# hamilton.net
KiCad netlist of a schematic drawn in EAGLE
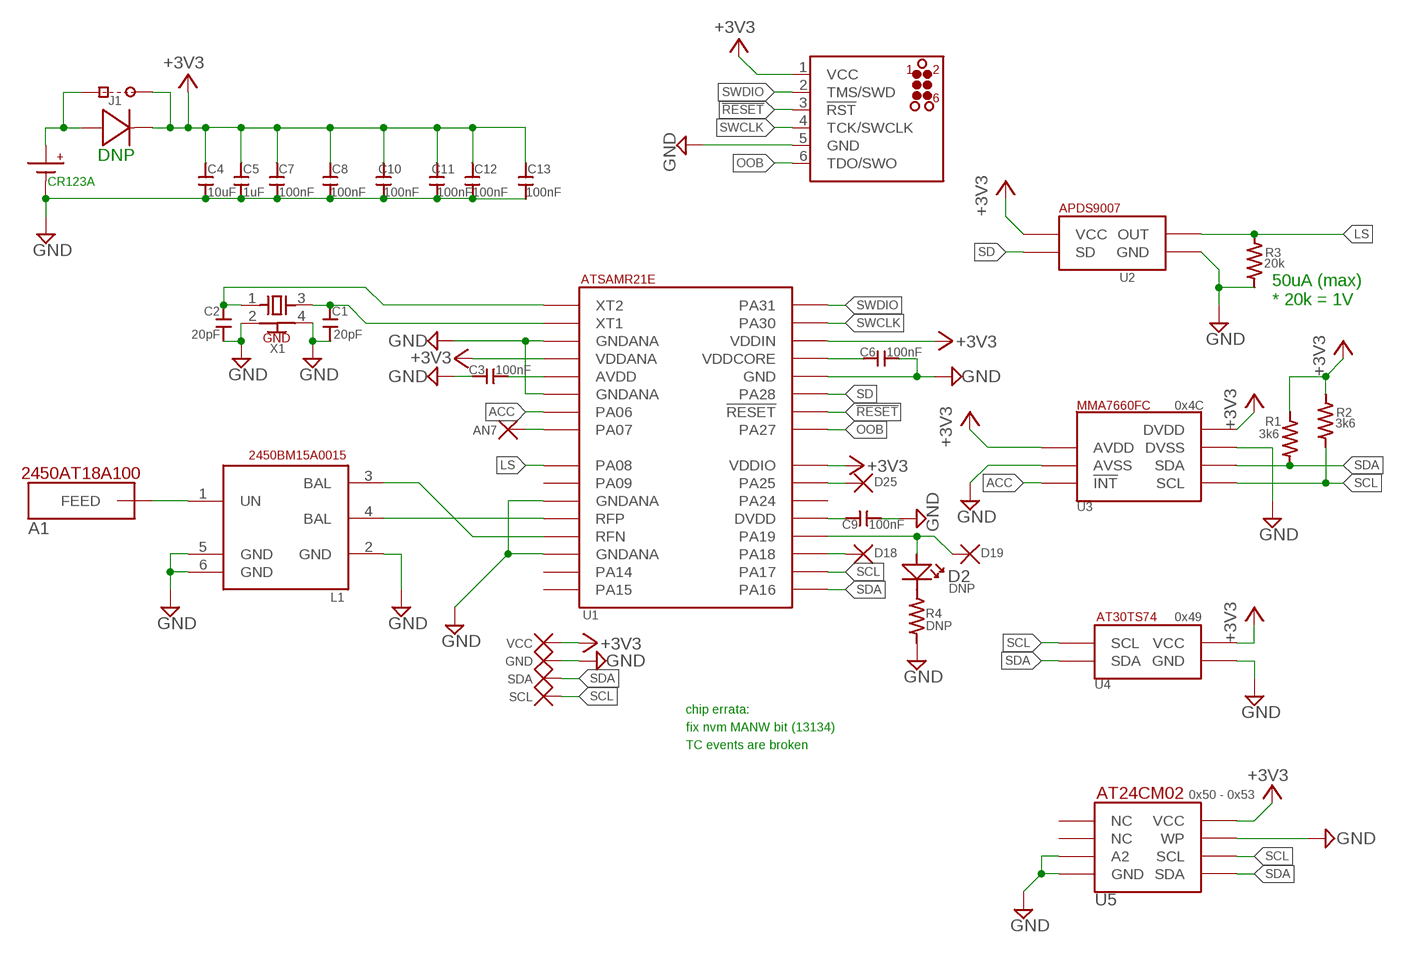
[diagram p0: schematic, sheet 1]

(export (version "E")
  (design (tool "Eeschema 10.0.6"))
  (components
    (comp (ref "A1")
      (value "JOHANSON_ANTENNA2")
      (footprint "eagle-import:JOHANSON_ANTENNA2")
      (libsource (lib "eagle-import") (part "JOHANSON_ANTENNA2"))
    )
    (comp (ref "BT1")
      (value "2/3A")
      (footprint "eagle-import:2_3A")
      (libsource (lib "eagle-import") (part "2/3A"))
    )
    (comp (ref "C1")
      (value "20pF")
      (footprint "eagle-import:S0402")
      (libsource (lib "eagle-import") (part "0603_CAPACITORSMALL"))
    )
    (comp (ref "C2")
      (value "20pF")
      (footprint "eagle-import:S0402")
      (libsource (lib "eagle-import") (part "0603_CAPACITORSMALL"))
    )
    (comp (ref "C3")
      (value "100nF")
      (footprint "eagle-import:C0402")
      (libsource (lib "eagle-import") (part "0603_CAPACITOR0402"))
    )
    (comp (ref "C4")
      (value "10uF")
      (footprint "eagle-import:0805")
      (libsource (lib "eagle-import") (part "0805_CAPACITOR"))
    )
    (comp (ref "C5")
      (value "1uF")
      (footprint "eagle-import:C0402")
      (libsource (lib "eagle-import") (part "0603_CAPACITOR0402"))
    )
    (comp (ref "C6")
      (value "100nF")
      (footprint "eagle-import:C0402")
      (libsource (lib "eagle-import") (part "0603_CAPACITOR0402"))
    )
    (comp (ref "C7")
      (value "100nF")
      (footprint "eagle-import:C0402")
      (libsource (lib "eagle-import") (part "0603_CAPACITOR0402"))
    )
    (comp (ref "C8")
      (value "100nF")
      (footprint "eagle-import:C0402")
      (libsource (lib "eagle-import") (part "0603_CAPACITOR0402"))
    )
    (comp (ref "C9")
      (value "100nF")
      (footprint "eagle-import:C0402")
      (libsource (lib "eagle-import") (part "0603_CAPACITOR0402"))
    )
    (comp (ref "C10")
      (value "100nF")
      (footprint "eagle-import:C0402")
      (libsource (lib "eagle-import") (part "0603_CAPACITOR0402"))
    )
    (comp (ref "C11")
      (value "100nF")
      (footprint "eagle-import:C0402")
      (libsource (lib "eagle-import") (part "0603_CAPACITOR0402"))
    )
    (comp (ref "C12")
      (value "100nF")
      (footprint "eagle-import:C0402")
      (libsource (lib "eagle-import") (part "0603_CAPACITOR0402"))
    )
    (comp (ref "C13")
      (value "100nF")
      (footprint "eagle-import:C0402")
      (libsource (lib "eagle-import") (part "0603_CAPACITOR0402"))
    )
    (comp (ref "D1")
      (value "SOD523F")
      (footprint "eagle-import:SOD523F")
      (libsource (lib "eagle-import") (part "SOD523F"))
    )
    (comp (ref "D2")
      (value "DNP")
      (footprint "eagle-import:LINE_0805")
      (libsource (lib "eagle-import") (part "STATLED"))
    )
    (comp (ref "J1")
      (value "CUTJ2")
      (footprint "eagle-import:CUT3")
      (libsource (lib "eagle-import") (part "CUTJ2"))
    )
    (comp (ref "L1")
      (value "BALUN_JOHANSON")
      (footprint "eagle-import:BALUN_JOHANSON")
      (libsource (lib "eagle-import") (part "BALUN_JOHANSON"))
    )
    (comp (ref "R1")
      (value "3k6")
      (footprint "eagle-import:S0402")
      (libsource (lib "eagle-import") (part "0603_RESISTORSMALL"))
    )
    (comp (ref "R2")
      (value "3k6")
      (footprint "eagle-import:S0402")
      (libsource (lib "eagle-import") (part "0603_RESISTORSMALL"))
    )
    (comp (ref "R3")
      (value "20k")
      (footprint "eagle-import:S0402")
      (libsource (lib "eagle-import") (part "0603_RESISTORSMALL"))
    )
    (comp (ref "R4")
      (value "DNP")
      (footprint "eagle-import:S0402")
      (libsource (lib "eagle-import") (part "0603_RESISTORSMALL"))
    )
    (comp (ref "TP1")
      (value "D19")
      (footprint "eagle-import:TPP")
      (libsource (lib "eagle-import") (part "TP"))
    )
    (comp (ref "TP2")
      (value "D18")
      (footprint "eagle-import:TPP")
      (libsource (lib "eagle-import") (part "TP"))
    )
    (comp (ref "TP3")
      (value "AN7")
      (footprint "eagle-import:TPP")
      (libsource (lib "eagle-import") (part "TP"))
    )
    (comp (ref "TP4")
      (value "D25")
      (footprint "eagle-import:TPP")
      (libsource (lib "eagle-import") (part "TP"))
    )
    (comp (ref "TP5")
      (value "VCC")
      (footprint "eagle-import:TPP")
      (libsource (lib "eagle-import") (part "TP"))
    )
    (comp (ref "TP6")
      (value "GND")
      (footprint "eagle-import:TPP")
      (libsource (lib "eagle-import") (part "TP"))
    )
    (comp (ref "TP7")
      (value "SDA")
      (footprint "eagle-import:TPP")
      (libsource (lib "eagle-import") (part "TP"))
    )
    (comp (ref "TP8")
      (value "SCL")
      (footprint "eagle-import:TPP")
      (libsource (lib "eagle-import") (part "TP"))
    )
    (comp (ref "U$1")
      (value "JLINK_CONNECT")
      (footprint "eagle-import:TC2030-MCP-NL")
      (libsource (lib "eagle-import") (part "JLINK_CONNECT"))
    )
    (comp (ref "U1")
      (value "SAMR21")
      (footprint "eagle-import:QFN32")
      (libsource (lib "eagle-import") (part "SAMR21"))
    )
    (comp (ref "U2")
      (value "APDS9007")
      (footprint "eagle-import:APDS9007")
      (libsource (lib "eagle-import") (part "APDS9007"))
    )
    (comp (ref "U3")
      (value "MMA7660FC")
      (footprint "eagle-import:MMA7660")
      (libsource (lib "eagle-import") (part "MMA7660FC"))
    )
    (comp (ref "U4")
      (value "AT30TS74")
      (footprint "eagle-import:4WLCSP")
      (libsource (lib "eagle-import") (part "AT30TS74"))
    )
    (comp (ref "U5")
      (value "AT24CM02")
      (footprint "eagle-import:SO8")
      (libsource (lib "eagle-import") (part "AT24CM02"))
    )
    (comp (ref "X1")
      (value "XTAL")
      (footprint "eagle-import:XTAL")
      (libsource (lib "eagle-import") (part "XTAL"))
    )
  )
  (nets
    (net (code "1") (name "+3V3") (class "Default")
      (node (ref "C10") (pin "1") (pinfunction "P$1_1") (pintype "passive"))
      (node (ref "C11") (pin "1") (pinfunction "P$1_1") (pintype "passive"))
      (node (ref "C12") (pin "1") (pinfunction "P$1_1") (pintype "passive"))
      (node (ref "C13") (pin "1") (pinfunction "P$1_1") (pintype "passive"))
      (node (ref "C4") (pin "2") (pinfunction "P$2_2") (pintype "passive"))
      (node (ref "C5") (pin "2") (pinfunction "P$2_2") (pintype "passive"))
      (node (ref "C7") (pin "1") (pinfunction "P$1_1") (pintype "passive"))
      (node (ref "C8") (pin "1") (pinfunction "P$1_1") (pintype "passive"))
      (node (ref "D1") (pin "NEG") (pinfunction "NEG_NEG") (pintype "passive"))
      (node (ref "J1") (pin "P$1") (pinfunction "R_P$1") (pintype "bidirectional"))
      (node (ref "R1") (pin "P$2") (pinfunction "P$2_P$2") (pintype "passive"))
      (node (ref "R2") (pin "P$2") (pinfunction "P$2_P$2") (pintype "passive"))
      (node (ref "TP5") (pin "P$1") (pinfunction "P$1_P$1") (pintype "bidirectional"))
      (node (ref "U$1") (pin "1") (pinfunction "VCC_1") (pintype "passive"))
      (node (ref "U1") (pin "24") (pinfunction "VDDIO_24") (pintype "bidirectional"))
      (node (ref "U1") (pin "30") (pinfunction "VDDIN_30") (pintype "bidirectional"))
      (node (ref "U1") (pin "4") (pinfunction "VDDANA_4") (pintype "bidirectional"))
      (node (ref "U2") (pin "4") (pinfunction "VCC_4") (pintype "bidirectional"))
      (node (ref "U3") (pin "3") (pinfunction "AVDD_3") (pintype "bidirectional"))
      (node (ref "U3") (pin "9") (pinfunction "DVDD_9") (pintype "bidirectional"))
      (node (ref "U4") (pin "A1") (pinfunction "VCC_A1") (pintype "bidirectional"))
      (node (ref "U5") (pin "8") (pinfunction "VCC_8") (pintype "bidirectional"))
    )
    (net (code "2") (name "/~{RESET}") (class "Default")
      (node (ref "U$1") (pin "3") (pinfunction "~{RST}_3") (pintype "bidirectional"))
      (node (ref "U1") (pin "26") (pinfunction "~{RESET}_26") (pintype "bidirectional"))
    )
    (net (code "3") (name "ACC") (class "Default")
      (node (ref "U1") (pin "7") (pinfunction "PA06_7") (pintype "bidirectional"))
      (node (ref "U3") (pin "5") (pinfunction "~{INT}_5") (pintype "bidirectional"))
    )
    (net (code "4") (name "GND") (class "Default")
      (node (ref "BT1") (pin "NEG") (pinfunction "-_NEG") (pintype "bidirectional"))
      (node (ref "C1") (pin "P$1") (pinfunction "P$1_P$1") (pintype "passive"))
      (node (ref "C10") (pin "2") (pinfunction "P$2_2") (pintype "passive"))
      (node (ref "C11") (pin "2") (pinfunction "P$2_2") (pintype "passive"))
      (node (ref "C12") (pin "2") (pinfunction "P$2_2") (pintype "passive"))
      (node (ref "C13") (pin "2") (pinfunction "P$2_2") (pintype "passive"))
      (node (ref "C2") (pin "P$1") (pinfunction "P$1_P$1") (pintype "passive"))
      (node (ref "C3") (pin "2") (pinfunction "P$2_2") (pintype "passive"))
      (node (ref "C4") (pin "1") (pinfunction "P$1_1") (pintype "passive"))
      (node (ref "C5") (pin "1") (pinfunction "P$1_1") (pintype "passive"))
      (node (ref "C6") (pin "1") (pinfunction "P$1_1") (pintype "passive"))
      (node (ref "C7") (pin "2") (pinfunction "P$2_2") (pintype "passive"))
      (node (ref "C8") (pin "2") (pinfunction "P$2_2") (pintype "passive"))
      (node (ref "C9") (pin "1") (pinfunction "P$1_1") (pintype "passive"))
      (node (ref "L1") (pin "2") (pinfunction "GND_2") (pintype "bidirectional"))
      (node (ref "L1") (pin "5") (pinfunction "GND_5") (pintype "bidirectional"))
      (node (ref "L1") (pin "6") (pinfunction "GND_6") (pintype "bidirectional"))
      (node (ref "R3") (pin "P$1") (pinfunction "P$1_P$1") (pintype "passive"))
      (node (ref "R4") (pin "P$1") (pinfunction "P$1_P$1") (pintype "passive"))
      (node (ref "TP6") (pin "P$1") (pinfunction "P$1_P$1") (pintype "bidirectional"))
      (node (ref "U$1") (pin "5") (pinfunction "GND_5") (pintype "power_in"))
      (node (ref "U1") (pin "11") (pinfunction "GNDANA_11") (pintype "bidirectional"))
      (node (ref "U1") (pin "14") (pinfunction "GNDANA_14") (pintype "bidirectional"))
      (node (ref "U1") (pin "28") (pinfunction "GND_28") (pintype "bidirectional"))
      (node (ref "U1") (pin "3") (pinfunction "GNDANA_3") (pintype "bidirectional"))
      (node (ref "U1") (pin "6") (pinfunction "GNDANA_6") (pintype "bidirectional"))
      (node (ref "U2") (pin "1") (pinfunction "GND_1") (pintype "bidirectional"))
      (node (ref "U3") (pin "4") (pinfunction "AVSS_4") (pintype "bidirectional"))
      (node (ref "U3") (pin "8") (pinfunction "DVSS_8") (pintype "bidirectional"))
      (node (ref "U4") (pin "A2") (pinfunction "GND_A2") (pintype "bidirectional"))
      (node (ref "U5") (pin "3") (pinfunction "A2_3") (pintype "bidirectional"))
      (node (ref "U5") (pin "4") (pinfunction "GND_4") (pintype "bidirectional"))
      (node (ref "U5") (pin "7") (pinfunction "WP_7") (pintype "bidirectional"))
      (node (ref "X1") (pin "2") (pinfunction "GND_2") (pintype "power_in"))
      (node (ref "X1") (pin "4") (pinfunction "GND_4") (pintype "power_in"))
    )
    (net (code "5") (name "LS") (class "Default")
      (node (ref "R3") (pin "P$2") (pinfunction "P$2_P$2") (pintype "passive"))
      (node (ref "U1") (pin "9") (pinfunction "PA08_9") (pintype "bidirectional"))
      (node (ref "U2") (pin "3") (pinfunction "OUT_3") (pintype "bidirectional"))
    )
    (net (code "6") (name "Net-(BT1-+)") (class "Default")
      (node (ref "BT1") (pin "POS") (pinfunction "+_POS") (pintype "bidirectional"))
      (node (ref "D1") (pin "POS") (pinfunction "POS_POS") (pintype "passive"))
      (node (ref "J1") (pin "P$2") (pinfunction "SQ_P$2") (pintype "bidirectional"))
    )
    (net (code "7") (name "Net-(C3-P$1)") (class "Default")
      (node (ref "C3") (pin "1") (pinfunction "P$1_1") (pintype "passive"))
      (node (ref "U1") (pin "5") (pinfunction "AVDD_5") (pintype "bidirectional"))
    )
    (net (code "8") (name "Net-(C6-P$2)") (class "Default")
      (node (ref "C6") (pin "2") (pinfunction "P$2_2") (pintype "passive"))
      (node (ref "U1") (pin "29") (pinfunction "VDDCORE_29") (pintype "bidirectional"))
    )
    (net (code "9") (name "Net-(C9-P$2)") (class "Default")
      (node (ref "C9") (pin "2") (pinfunction "P$2_2") (pintype "passive"))
      (node (ref "U1") (pin "21") (pinfunction "DVDD_21") (pintype "bidirectional"))
    )
    (net (code "10") (name "Net-(D2-+)") (class "Default")
      (node (ref "D2") (pin "NOLINE") (pinfunction "+_NOLINE") (pintype "passive"))
      (node (ref "TP1") (pin "P$1") (pinfunction "P$1_P$1") (pintype "bidirectional"))
      (node (ref "U1") (pin "20") (pinfunction "PA19_20") (pintype "bidirectional"))
    )
    (net (code "11") (name "Net-(D2--)") (class "Default")
      (node (ref "D2") (pin "LINE") (pinfunction "-_LINE") (pintype "passive"))
      (node (ref "R4") (pin "P$2") (pinfunction "P$2_P$2") (pintype "passive"))
    )
    (net (code "12") (name "Net-(L1-UN)") (class "Default")
      (node (ref "A1") (pin "FEED") (pinfunction "FEED_FEED") (pintype "bidirectional"))
      (node (ref "L1") (pin "1") (pinfunction "UN_1") (pintype "bidirectional"))
    )
    (net (code "13") (name "Net-(U1-PA07)") (class "Default")
      (node (ref "TP3") (pin "P$1") (pinfunction "P$1_P$1") (pintype "bidirectional"))
      (node (ref "U1") (pin "8") (pinfunction "PA07_8") (pintype "bidirectional"))
    )
    (net (code "14") (name "Net-(U1-PA18)") (class "Default")
      (node (ref "TP2") (pin "P$1") (pinfunction "P$1_P$1") (pintype "bidirectional"))
      (node (ref "U1") (pin "19") (pinfunction "PA18_19") (pintype "bidirectional"))
    )
    (net (code "15") (name "Net-(U1-PA25)") (class "Default")
      (node (ref "TP4") (pin "P$1") (pinfunction "P$1_P$1") (pintype "bidirectional"))
      (node (ref "U1") (pin "23") (pinfunction "PA25_23") (pintype "bidirectional"))
    )
    (net (code "16") (name "Net-(U1-RFN)") (class "Default")
      (node (ref "L1") (pin "3") (pinfunction "BAL_3") (pintype "bidirectional"))
      (node (ref "U1") (pin "13") (pinfunction "RFN_13") (pintype "bidirectional"))
    )
    (net (code "17") (name "Net-(U1-RFP)") (class "Default")
      (node (ref "L1") (pin "4") (pinfunction "BAL_4") (pintype "bidirectional"))
      (node (ref "U1") (pin "12") (pinfunction "RFP_12") (pintype "bidirectional"))
    )
    (net (code "18") (name "Net-(U1-XT1)") (class "Default")
      (node (ref "C1") (pin "P$2") (pinfunction "P$2_P$2") (pintype "passive"))
      (node (ref "U1") (pin "2") (pinfunction "XT1_2") (pintype "bidirectional"))
      (node (ref "X1") (pin "3") (pinfunction "X2_3") (pintype "power_in"))
    )
    (net (code "19") (name "Net-(U1-XT2)") (class "Default")
      (node (ref "C2") (pin "P$2") (pinfunction "P$2_P$2") (pintype "passive"))
      (node (ref "U1") (pin "1") (pinfunction "XT2_1") (pintype "bidirectional"))
      (node (ref "X1") (pin "1") (pinfunction "X1_1") (pintype "power_in"))
    )
    (net (code "20") (name "OOB") (class "Default")
      (node (ref "U$1") (pin "6") (pinfunction "TDO/SWO_6") (pintype "bidirectional"))
      (node (ref "U1") (pin "25") (pinfunction "PA27_25") (pintype "bidirectional"))
    )
    (net (code "21") (name "SCL") (class "Default")
      (node (ref "R2") (pin "P$1") (pinfunction "P$1_P$1") (pintype "passive"))
      (node (ref "TP8") (pin "P$1") (pinfunction "P$1_P$1") (pintype "bidirectional"))
      (node (ref "U1") (pin "18") (pinfunction "PA17_18") (pintype "bidirectional"))
      (node (ref "U3") (pin "6") (pinfunction "SCL_6") (pintype "bidirectional"))
      (node (ref "U4") (pin "B2") (pinfunction "SCL_B2") (pintype "bidirectional"))
      (node (ref "U5") (pin "6") (pinfunction "SCL_6") (pintype "bidirectional"))
    )
    (net (code "22") (name "SD") (class "Default")
      (node (ref "U1") (pin "27") (pinfunction "PA28_27") (pintype "bidirectional"))
      (node (ref "U2") (pin "6") (pinfunction "SD_6") (pintype "bidirectional"))
    )
    (net (code "23") (name "SDA") (class "Default")
      (node (ref "R1") (pin "P$1") (pinfunction "P$1_P$1") (pintype "passive"))
      (node (ref "TP7") (pin "P$1") (pinfunction "P$1_P$1") (pintype "bidirectional"))
      (node (ref "U1") (pin "17") (pinfunction "PA16_17") (pintype "bidirectional"))
      (node (ref "U3") (pin "7") (pinfunction "SDA_7") (pintype "bidirectional"))
      (node (ref "U4") (pin "B1") (pinfunction "SDA_B1") (pintype "bidirectional"))
      (node (ref "U5") (pin "5") (pinfunction "SDA_5") (pintype "bidirectional"))
    )
    (net (code "24") (name "SWCLK") (class "Default")
      (node (ref "U$1") (pin "4") (pinfunction "TCK/SWCLK_4") (pintype "bidirectional"))
      (node (ref "U1") (pin "31") (pinfunction "PA30_31") (pintype "bidirectional"))
    )
    (net (code "25") (name "SWDIO") (class "Default")
      (node (ref "U$1") (pin "2") (pinfunction "TMS/SWD_2") (pintype "bidirectional"))
      (node (ref "U1") (pin "32") (pinfunction "PA31_32") (pintype "bidirectional"))
    )
    (net (code "26") (name "unconnected-(U1-PA09-Pad10)") (class "Default")
      (node (ref "U1") (pin "10") (pinfunction "PA09_10") (pintype "bidirectional"))
    )
    (net (code "27") (name "unconnected-(U1-PA14-Pad15)") (class "Default")
      (node (ref "U1") (pin "15") (pinfunction "PA14_15") (pintype "bidirectional"))
    )
    (net (code "28") (name "unconnected-(U1-PA15-Pad16)") (class "Default")
      (node (ref "U1") (pin "16") (pinfunction "PA15_16") (pintype "bidirectional"))
    )
    (net (code "29") (name "unconnected-(U1-PA24-Pad22)") (class "Default")
      (node (ref "U1") (pin "22") (pinfunction "PA24_22") (pintype "bidirectional"))
    )
    (net (code "30") (name "unconnected-(U5-NC-Pad1)") (class "Default")
      (node (ref "U5") (pin "1") (pinfunction "NC_1") (pintype "bidirectional"))
    )
    (net (code "31") (name "unconnected-(U5-NC-Pad2)") (class "Default")
      (node (ref "U5") (pin "2") (pinfunction "NC_2") (pintype "bidirectional"))
    )
  )
)
